# 16_LMS2_RF2_Misc.net
KiCad netlist of a schematic drawn in Altium Designer
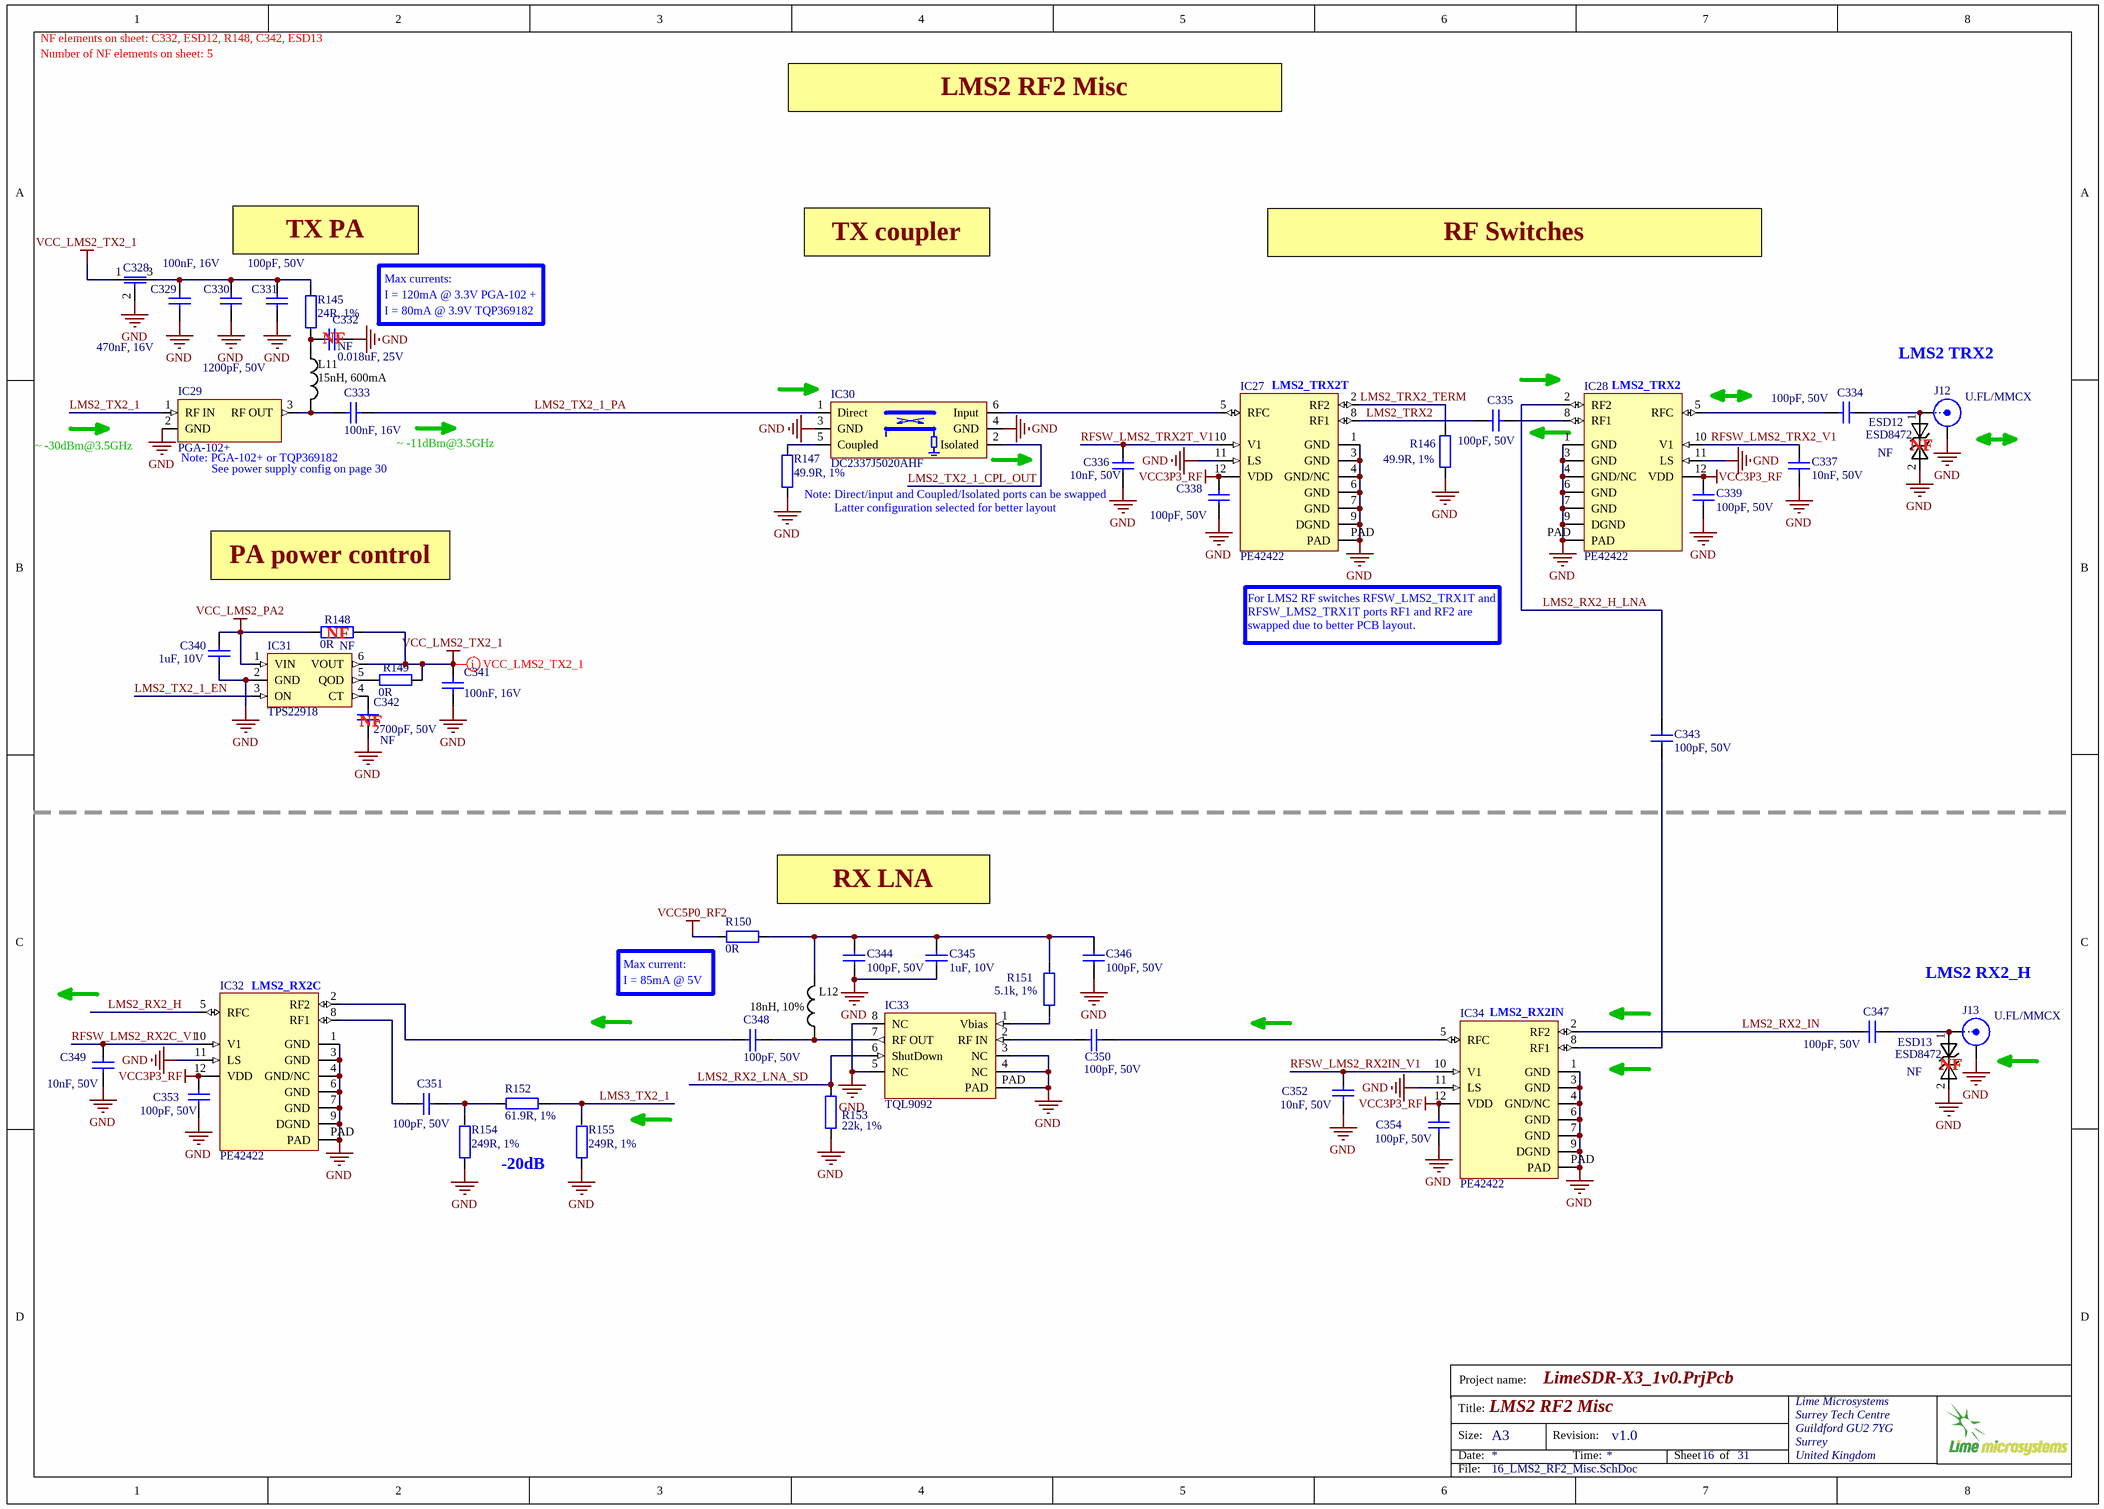
[diagram p0: 16_LMS2_RF2_Misc.SchDoc]

(export (version "E")
  (design (tool "Eeschema 10.0.6"))
  (components
    (comp (ref "C328")
      (value "470nF, 16V")
      (footprint "CAP0805_FEEDTHROUGH")
      (fields
        (field (name "MANUFACTURER") "Murata")
        (field (name "TOLERANCE") "20%")
        (field (name "VOLTAGE") "16V")
      )
      (libsource (lib "LimeMicroAltiumLib_schLib_r01") (part "Cap_feed_through"))
    )
    (comp (ref "C329")
      (value "100nF, 16V")
      (footprint "CAP0402")
      (fields (field (name "MANUFACTURER") "Murata Electronics") (field (name "TOLERANCE") "10 %"))
      (libsource (lib "") (part "Cap_0402_6"))
    )
    (comp (ref "C330")
      (value "1200pF, 50V")
      (footprint "CAP0402")
      (fields (field (name "MANUFACTURER") "Kemet") (field (name "TOLERANCE") "±5%"))
      (libsource (lib "") (part "Cap_0402_5"))
    )
    (comp (ref "C331")
      (value "100pF, 50V")
      (footprint "CAP0402")
      (fields (field (name "TOLERANCE") "±5%") (field (name "MANUFACTURER") "Yageo"))
      (libsource (lib "") (part "Cap_0402_6"))
    )
    (comp (ref "C332")
      (value "0.018uF, 25V")
      (footprint "CAP0402")
      (fields
        (field (name "ASSEMBLY INFO") "NF")
        (field (name "MANUFACTURER") "Yageo")
        (field (name "TOLERANCE") "10%")
      )
      (libsource (lib "") (part "Cap_0402_5"))
    )
    (comp (ref "C333")
      (value "100nF, 16V")
      (footprint "CAP0402")
      (fields (field (name "MANUFACTURER") "Murata Electronics") (field (name "TOLERANCE") "10 %"))
      (libsource (lib "") (part "Cap_0402_5"))
    )
    (comp (ref "C334")
      (value "100pF, 50V")
      (footprint "CAP0402")
      (fields (field (name "TOLERANCE") "±5%") (field (name "MANUFACTURER") "Yageo"))
      (libsource (lib "LimeMicroAltiumLib_schLib") (part "Cap_0402"))
    )
    (comp (ref "C335")
      (value "100pF, 50V")
      (footprint "CAP0402")
      (fields (field (name "TOLERANCE") "±5%") (field (name "MANUFACTURER") "Yageo"))
      (libsource (lib "LimeMicroAltiumLib_schLib") (part "Cap_0402"))
    )
    (comp (ref "C336")
      (value "10nF, 50V")
      (footprint "CAP0402")
      (fields
        (field (name "MANUFACTURER") "Murata Electronics North America")
        (field (name "TOLERANCE") "±10%")
      )
      (libsource (lib "") (part "Cap_0402_1"))
    )
    (comp (ref "C337")
      (value "10nF, 50V")
      (footprint "CAP0402")
      (fields
        (field (name "MANUFACTURER") "Murata Electronics North America")
        (field (name "TOLERANCE") "±10%")
      )
      (libsource (lib "") (part "Cap_0402_1"))
    )
    (comp (ref "C338")
      (value "100pF, 50V")
      (footprint "CAP0402")
      (fields (field (name "TOLERANCE") "±5%") (field (name "MANUFACTURER") "Yageo"))
      (libsource (lib "") (part "Cap_0402_10"))
    )
    (comp (ref "C339")
      (value "100pF, 50V")
      (footprint "CAP0402")
      (fields (field (name "TOLERANCE") "±5%") (field (name "MANUFACTURER") "Yageo"))
      (libsource (lib "") (part "Cap_0402_10"))
    )
    (comp (ref "C340")
      (value "1uF, 10V")
      (footprint "CAP0402")
      (fields (field (name "MANUFACTURER") "TDK"))
      (libsource (lib "") (part "Cap_0402_2"))
    )
    (comp (ref "C341")
      (value "100nF, 16V")
      (footprint "CAP0402")
      (fields (field (name "MANUFACTURER") "Murata Electronics") (field (name "TOLERANCE") "10 %"))
      (libsource (lib "") (part "Cap_0402_2"))
    )
    (comp (ref "C342")
      (value "2700pF, 50V")
      (footprint "CAP0402")
      (fields
        (field (name "ASSEMBLY INFO") "NF")
        (field (name "TOLERANCE") "±10%")
        (field (name "MANUFACTURER") "Murata Electronics North America")
      )
      (libsource (lib "") (part "Cap_0402_6"))
    )
    (comp (ref "C343")
      (value "100pF, 50V")
      (footprint "CAP0402")
      (fields (field (name "TOLERANCE") "±5%") (field (name "MANUFACTURER") "Yageo"))
      (libsource (lib "LimeMicroAltiumLib_schLib") (part "Cap_0402"))
    )
    (comp (ref "C344")
      (value "100pF, 50V")
      (footprint "CAP0402")
      (fields (field (name "TOLERANCE") "±5%") (field (name "MANUFACTURER") "Yageo"))
      (libsource (lib "") (part "Cap_0402_3"))
    )
    (comp (ref "C345")
      (value "1uF, 10V")
      (footprint "CAP0402")
      (fields (field (name "MANUFACTURER") "TDK"))
      (libsource (lib "") (part "Cap_0402_4"))
    )
    (comp (ref "C346")
      (value "100pF, 50V")
      (footprint "CAP0402")
      (fields (field (name "TOLERANCE") "±5%") (field (name "MANUFACTURER") "Yageo"))
      (libsource (lib "") (part "Cap_0402_3"))
    )
    (comp (ref "C347")
      (value "100pF, 50V")
      (footprint "CAP0402")
      (fields (field (name "TOLERANCE") "±5%") (field (name "MANUFACTURER") "Yageo"))
      (libsource (lib "LimeMicroAltiumLib_schLib") (part "Cap_0402"))
    )
    (comp (ref "C348")
      (value "100pF, 50V")
      (footprint "CAP0402")
      (fields (field (name "TOLERANCE") "±5%") (field (name "MANUFACTURER") "Yageo"))
      (libsource (lib "") (part "Cap_0402_2"))
    )
    (comp (ref "C349")
      (value "10nF, 50V")
      (footprint "CAP0402")
      (fields
        (field (name "MANUFACTURER") "Murata Electronics North America")
        (field (name "TOLERANCE") "±10%")
      )
      (libsource (lib "") (part "Cap_0402_8"))
    )
    (comp (ref "C350")
      (value "100pF, 50V")
      (footprint "CAP0402")
      (fields (field (name "TOLERANCE") "±5%") (field (name "MANUFACTURER") "Yageo"))
      (libsource (lib "") (part "Cap_0402_7"))
    )
    (comp (ref "C351")
      (value "100pF, 50V")
      (footprint "CAP0402")
      (fields (field (name "TOLERANCE") "±5%") (field (name "MANUFACTURER") "Yageo"))
      (libsource (lib "LimeMicroAltiumLib_schLib") (part "Cap_0402"))
    )
    (comp (ref "C352")
      (value "10nF, 50V")
      (footprint "CAP0402")
      (fields
        (field (name "MANUFACTURER") "Murata Electronics North America")
        (field (name "TOLERANCE") "±10%")
      )
      (libsource (lib "") (part "Cap_0402_5"))
    )
    (comp (ref "C353")
      (value "100pF, 50V")
      (footprint "CAP0402")
      (fields (field (name "TOLERANCE") "±5%") (field (name "MANUFACTURER") "Yageo"))
      (libsource (lib "") (part "Cap_0402_9"))
    )
    (comp (ref "C354")
      (value "100pF, 50V")
      (footprint "CAP0402")
      (fields (field (name "TOLERANCE") "±5%") (field (name "MANUFACTURER") "Yageo"))
      (libsource (lib "") (part "Cap_0402_5"))
    )
    (comp (ref "ESD12")
      (value "ESD8472")
      (footprint "ESD8472_X3DFN2")
      (fields (field (name "MANUFACTURER") "ON Semiconductor") (field (name "ASSEMBLY INFO") "NF"))
      (libsource (lib "LimeMicroAltiumLib_schLib") (part "ESD8472"))
    )
    (comp (ref "ESD13")
      (value "ESD8472")
      (footprint "ESD8472_X3DFN2")
      (fields (field (name "MANUFACTURER") "ON Semiconductor") (field (name "ASSEMBLY INFO") "NF"))
      (libsource (lib "") (part "ESD8472_1"))
    )
    (comp (ref "IC27")
      (value "PE42422")
      (footprint "PE42422_QFN12")
      (fields (field (name "MANUFACTURER") "Peregrine Semiconductor"))
      (libsource (lib "") (part "PE42422_1"))
    )
    (comp (ref "IC28")
      (value "PE42422")
      (footprint "PE42422_QFN12")
      (fields (field (name "MANUFACTURER") "Peregrine Semiconductor"))
      (libsource (lib "LimeMicroAltiumLib_schLib") (part "PE42422"))
    )
    (comp (ref "IC29")
      (value "PGA-102+")
      (footprint "PGA-102+_SOT89")
      (fields (field (name "MANUFACTURER") "Qorvo"))
      (libsource (lib "LimeMicroAltiumLib_schLib_r01") (part "PGA-102+_PA"))
    )
    (comp (ref "IC30")
      (value "DC2337J5020AHF")
      (footprint "DC2337J5020AHF_ANAREN_COUPLER_0805")
      (fields (field (name "MANUFACTURER") "Anaren"))
      (libsource (lib "LimeMicroAltiumLib_schLib_r02") (part "DC2337J5020AHF_coupler"))
    )
    (comp (ref "IC31")
      (value "TPS22918")
      (footprint "SOT23-6")
      (fields (field (name "MANUFACTURER") "Texas Instruments"))
      (libsource (lib "LimeMicroAltiumLib_schLib") (part "TPS22918"))
    )
    (comp (ref "IC32")
      (value "PE42422")
      (footprint "PE42422_QFN12")
      (fields (field (name "MANUFACTURER") "Peregrine Semiconductor"))
      (libsource (lib "") (part "PE42422_3"))
    )
    (comp (ref "IC33")
      (value "TQL9092")
      (footprint "TQL9092")
      (fields (field (name "MANUFACTURER") "Qorvo"))
      (libsource (lib "LimeMicroAltiumLib_schLib") (part "TQL9092"))
    )
    (comp (ref "IC34")
      (value "PE42422")
      (footprint "PE42422_QFN12")
      (fields (field (name "MANUFACTURER") "Peregrine Semiconductor"))
      (libsource (lib "") (part "PE42422_2"))
    )
    (comp (ref "J12")
      (value "U.FL/MMCX")
      (footprint "MMCX_UFL_conn_m")
      (description "CONN UMC RCPT STR 50 OHM SMD")
      (fields (field (name "MANUFACTURER") "Amphenol RF"))
      (libsource (lib "LimeMicroAltiumLib_schLib") (part "RF_IF_connector"))
    )
    (comp (ref "J13")
      (value "U.FL/MMCX")
      (footprint "MMCX_UFL_conn_m")
      (description "CONN UMC RCPT STR 50 OHM SMD")
      (fields (field (name "MANUFACTURER") "Amphenol RF"))
      (libsource (lib "LimeMicroAltiumLib_schLib") (part "RF_IF_connector"))
    )
    (comp (ref "L11")
      (value "15nH, 600mA")
      (footprint "RES0805")
      (fields (field (name "MANUFACTURER") "Bourns") (field (name "TOLERANCE") "5%"))
      (libsource (lib "LimeMicroAltiumLib_schLib") (part "Inductor_0603"))
    )
    (comp (ref "L12")
      (value "18nH, 10%")
      (footprint "RES0603")
      (fields (field (name "MANUFACTURER") "Pulse Electronics Network") (field (name "TOLERANCE") "±10%"))
      (libsource (lib "LimeMicroAltiumLib_schLib") (part "Inductor"))
    )
    (comp (ref "R145")
      (value "24R, 1%")
      (footprint "RES0402")
      (fields (field (name "MANUFACTURER") "Yageo") (field (name "TOLERANCE") "1%"))
      (libsource (lib "LimeFPGAboard_schLib") (part "Res_0402"))
    )
    (comp (ref "R146")
      (value "49.9R, 1%")
      (footprint "RES0402")
      (fields
        (field (name "TOLERANCE") "±1%")
        (field (name "MANUFACTURER") "Samsung Electro-Mechanics America, Inc.")
        (field (name "MANUFACTURER PART NUMBER") "RC1005F49R9CS")
      )
      (libsource (lib "LimeMicroAltiumLib_schLib") (part "Res_0402"))
    )
    (comp (ref "R147")
      (value "49.9R, 1%")
      (footprint "RES0402")
      (fields
        (field (name "TOLERANCE") "±1%")
        (field (name "MANUFACTURER") "Samsung Electro-Mechanics America, Inc.")
        (field (name "MANUFACTURER PART NUMBER") "RC1005F49R9CS")
      )
      (libsource (lib "LimeMicroAltiumLib_schLib") (part "Res_0402"))
    )
    (comp (ref "R148")
      (value "0R")
      (footprint "RES0402")
      (fields
        (field (name "ASSEMBLY INFO") "NF")
        (field (name "MANUFACTURER") "Yageo")
        (field (name "TOLERANCE") "Jumper")
      )
      (libsource (lib "") (part "Res_0402_1"))
    )
    (comp (ref "R149")
      (value "0R")
      (footprint "RES0402")
      (fields (field (name "MANUFACTURER") "Yageo") (field (name "TOLERANCE") "Jumper"))
      (libsource (lib "") (part "Res_0402_1"))
    )
    (comp (ref "R150")
      (value "0R")
      (footprint "RES0402")
      (fields (field (name "MANUFACTURER") "Yageo") (field (name "TOLERANCE") "Jumper"))
      (libsource (lib "LimeMicroAltiumLib_schLib") (part "Res_0402"))
    )
    (comp (ref "R151")
      (value "5.1k, 1%")
      (footprint "RES0603")
      (fields (field (name "MANUFACTURER") "Stackpole Electronics") (field (name "TOLERANCE") "1%"))
      (libsource (lib "LimeMicroAltiumLib_schLib") (part "Res_0603"))
    )
    (comp (ref "R152")
      (value "61.9R, 1%")
      (footprint "RES0402")
      (fields (field (name "MANUFACTURER") "Yageo") (field (name "TOLERANCE") "1%"))
      (libsource (lib "") (part "Res_0402_1"))
    )
    (comp (ref "R153")
      (value "22k, 1%")
      (footprint "RES0402")
      (fields (field (name "MANUFACTURER") "Yageo") (field (name "TOLERANCE") "±1%"))
      (libsource (lib "") (part "Res_0402_1"))
    )
    (comp (ref "R154")
      (value "249R, 1%")
      (footprint "RES0402")
      (fields (field (name "MANUFACTURER") "Stackpole Electronics Inc") (field (name "TOLERANCE") "±1%"))
      (libsource (lib "") (part "Res_0402_1"))
    )
    (comp (ref "R155")
      (value "249R, 1%")
      (footprint "RES0402")
      (fields (field (name "MANUFACTURER") "Stackpole Electronics Inc") (field (name "TOLERANCE") "±1%"))
      (libsource (lib "") (part "Res_0402_1"))
    )
  )
  (nets
    (net (code "1") (name "/LMS2_RX2_H") (class "Default")
      (node (ref "IC32") (pin "5") (pinfunction "RFC_5") (pintype "bidirectional"))
    )
    (net (code "2") (name "/LMS2_RX2_H_LNA") (class "Default")
      (node (ref "C343") (pin "2") (pinfunction "2_2") (pintype "passive"))
      (node (ref "IC28") (pin "2") (pinfunction "RF2_2") (pintype "bidirectional"))
    )
    (net (code "3") (name "/LMS2_RX2_IN") (class "Default")
      (node (ref "C347") (pin "1") (pinfunction "1_1") (pintype "passive"))
      (node (ref "IC34") (pin "2") (pinfunction "RF2_2") (pintype "bidirectional"))
    )
    (net (code "4") (name "/LMS2_RX2_LNA_SD") (class "Default")
      (node (ref "IC33") (pin "6") (pinfunction "ShutDown_6") (pintype "input"))
      (node (ref "R153") (pin "2") (pinfunction "2_2") (pintype "passive"))
    )
    (net (code "5") (name "/LMS2_TRX2") (class "Default")
      (node (ref "C335") (pin "1") (pinfunction "1_1") (pintype "passive"))
      (node (ref "IC27") (pin "8") (pinfunction "RF1_8") (pintype "bidirectional"))
    )
    (net (code "6") (name "/LMS2_TRX2_TERM") (class "Default")
      (node (ref "IC27") (pin "2") (pinfunction "RF2_2") (pintype "bidirectional"))
      (node (ref "R146") (pin "1") (pinfunction "1_1") (pintype "passive"))
    )
    (net (code "7") (name "/LMS2_TX2_1") (class "Default")
      (node (ref "IC29") (pin "1") (pinfunction "RF_IN_1") (pintype "input"))
    )
    (net (code "8") (name "/LMS2_TX2_1_CPL_OUT") (class "Default")
      (node (ref "IC30") (pin "2") (pinfunction "Isolated_2") (pintype "passive"))
    )
    (net (code "9") (name "/LMS2_TX2_1_EN") (class "Default")
      (node (ref "IC31") (pin "3") (pinfunction "ON_3") (pintype "input"))
    )
    (net (code "10") (name "/LMS2_TX2_1_PA") (class "Default")
      (node (ref "C333") (pin "1") (pinfunction "1_1") (pintype "passive"))
      (node (ref "IC30") (pin "1") (pinfunction "Direct_1") (pintype "passive"))
    )
    (net (code "11") (name "/LMS3_TX2_1") (class "Default")
      (node (ref "R152") (pin "2") (pinfunction "2_2") (pintype "passive"))
      (node (ref "R155") (pin "2") (pinfunction "2_2") (pintype "passive"))
    )
    (net (code "12") (name "/RFSW_LMS2_RX2C_V1") (class "Default")
      (node (ref "C349") (pin "1") (pinfunction "1_1") (pintype "passive"))
      (node (ref "IC32") (pin "10") (pinfunction "V1_10") (pintype "input"))
    )
    (net (code "13") (name "/RFSW_LMS2_RX2IN_V1") (class "Default")
      (node (ref "C352") (pin "1") (pinfunction "1_1") (pintype "passive"))
      (node (ref "IC34") (pin "10") (pinfunction "V1_10") (pintype "input"))
    )
    (net (code "14") (name "/RFSW_LMS2_TRX2T_V1") (class "Default")
      (node (ref "C336") (pin "1") (pinfunction "1_1") (pintype "passive"))
      (node (ref "IC27") (pin "10") (pinfunction "V1_10") (pintype "input"))
    )
    (net (code "15") (name "/RFSW_LMS2_TRX2_V1") (class "Default")
      (node (ref "C337") (pin "1") (pinfunction "1_1") (pintype "passive"))
      (node (ref "IC28") (pin "10") (pinfunction "V1_10") (pintype "input"))
    )
    (net (code "16") (name "GND") (class "Default")
      (node (ref "C328") (pin "2") (pinfunction "2_2") (pintype "passive"))
      (node (ref "C329") (pin "1") (pinfunction "1_1") (pintype "passive"))
      (node (ref "C330") (pin "2") (pinfunction "2_2") (pintype "passive"))
      (node (ref "C331") (pin "2") (pinfunction "2_2") (pintype "passive"))
      (node (ref "C332") (pin "2") (pinfunction "2_2") (pintype "passive"))
      (node (ref "C336") (pin "2") (pinfunction "2_2") (pintype "passive"))
      (node (ref "C337") (pin "2") (pinfunction "2_2") (pintype "passive"))
      (node (ref "C338") (pin "1") (pinfunction "1_1") (pintype "passive"))
      (node (ref "C339") (pin "1") (pinfunction "1_1") (pintype "passive"))
      (node (ref "C340") (pin "1") (pinfunction "1_1") (pintype "passive"))
      (node (ref "C341") (pin "1") (pinfunction "1_1") (pintype "passive"))
      (node (ref "C342") (pin "2") (pinfunction "2_2") (pintype "passive"))
      (node (ref "C344") (pin "2") (pinfunction "2_2") (pintype "passive"))
      (node (ref "C345") (pin "1") (pinfunction "1_1") (pintype "passive"))
      (node (ref "C346") (pin "2") (pinfunction "2_2") (pintype "passive"))
      (node (ref "C349") (pin "2") (pinfunction "2_2") (pintype "passive"))
      (node (ref "C352") (pin "2") (pinfunction "2_2") (pintype "passive"))
      (node (ref "C353") (pin "1") (pinfunction "1_1") (pintype "passive"))
      (node (ref "C354") (pin "1") (pinfunction "1_1") (pintype "passive"))
      (node (ref "ESD12") (pin "2") (pinfunction "2_2") (pintype "passive"))
      (node (ref "ESD13") (pin "2") (pinfunction "2_2") (pintype "passive"))
      (node (ref "IC27") (pin "1") (pinfunction "GND_1") (pintype "passive"))
      (node (ref "IC27") (pin "11") (pinfunction "LS_11") (pintype "input"))
      (node (ref "IC27") (pin "3") (pinfunction "GND_3") (pintype "passive"))
      (node (ref "IC27") (pin "4") (pinfunction "GND/NC_4") (pintype "passive"))
      (node (ref "IC27") (pin "6") (pinfunction "GND_6") (pintype "passive"))
      (node (ref "IC27") (pin "7") (pinfunction "GND_7") (pintype "passive"))
      (node (ref "IC27") (pin "9") (pinfunction "DGND_9") (pintype "passive"))
      (node (ref "IC27") (pin "PAD") (pinfunction "PAD_PAD") (pintype "passive"))
      (node (ref "IC28") (pin "1") (pinfunction "GND_1") (pintype "passive"))
      (node (ref "IC28") (pin "11") (pinfunction "LS_11") (pintype "input"))
      (node (ref "IC28") (pin "3") (pinfunction "GND_3") (pintype "passive"))
      (node (ref "IC28") (pin "4") (pinfunction "GND/NC_4") (pintype "passive"))
      (node (ref "IC28") (pin "6") (pinfunction "GND_6") (pintype "passive"))
      (node (ref "IC28") (pin "7") (pinfunction "GND_7") (pintype "passive"))
      (node (ref "IC28") (pin "9") (pinfunction "DGND_9") (pintype "passive"))
      (node (ref "IC28") (pin "PAD") (pinfunction "PAD_PAD") (pintype "passive"))
      (node (ref "IC29") (pin "2") (pinfunction "GND_2") (pintype "passive"))
      (node (ref "IC30") (pin "3") (pinfunction "GND_3") (pintype "passive"))
      (node (ref "IC30") (pin "4") (pinfunction "GND_4") (pintype "passive"))
      (node (ref "IC31") (pin "2") (pinfunction "GND_2") (pintype "passive"))
      (node (ref "IC32") (pin "1") (pinfunction "GND_1") (pintype "passive"))
      (node (ref "IC32") (pin "11") (pinfunction "LS_11") (pintype "input"))
      (node (ref "IC32") (pin "3") (pinfunction "GND_3") (pintype "passive"))
      (node (ref "IC32") (pin "4") (pinfunction "GND/NC_4") (pintype "passive"))
      (node (ref "IC32") (pin "6") (pinfunction "GND_6") (pintype "passive"))
      (node (ref "IC32") (pin "7") (pinfunction "GND_7") (pintype "passive"))
      (node (ref "IC32") (pin "9") (pinfunction "DGND_9") (pintype "passive"))
      (node (ref "IC32") (pin "PAD") (pinfunction "PAD_PAD") (pintype "passive"))
      (node (ref "IC33") (pin "3") (pinfunction "NC_3") (pintype "passive"))
      (node (ref "IC33") (pin "4") (pinfunction "NC_4") (pintype "passive"))
      (node (ref "IC33") (pin "5") (pinfunction "NC_5") (pintype "passive"))
      (node (ref "IC33") (pin "8") (pinfunction "NC_8") (pintype "passive"))
      (node (ref "IC33") (pin "PAD") (pinfunction "PAD_PAD") (pintype "passive"))
      (node (ref "IC34") (pin "1") (pinfunction "GND_1") (pintype "passive"))
      (node (ref "IC34") (pin "11") (pinfunction "LS_11") (pintype "input"))
      (node (ref "IC34") (pin "3") (pinfunction "GND_3") (pintype "passive"))
      (node (ref "IC34") (pin "4") (pinfunction "GND/NC_4") (pintype "passive"))
      (node (ref "IC34") (pin "6") (pinfunction "GND_6") (pintype "passive"))
      (node (ref "IC34") (pin "7") (pinfunction "GND_7") (pintype "passive"))
      (node (ref "IC34") (pin "9") (pinfunction "DGND_9") (pintype "passive"))
      (node (ref "IC34") (pin "PAD") (pinfunction "PAD_PAD") (pintype "passive"))
      (node (ref "J12") (pin "2") (pinfunction "Y_2") (pintype "passive"))
      (node (ref "J13") (pin "2") (pinfunction "Y_2") (pintype "passive"))
      (node (ref "R146") (pin "2") (pinfunction "2_2") (pintype "passive"))
      (node (ref "R147") (pin "2") (pinfunction "2_2") (pintype "passive"))
      (node (ref "R153") (pin "1") (pinfunction "1_1") (pintype "passive"))
      (node (ref "R154") (pin "1") (pinfunction "1_1") (pintype "passive"))
      (node (ref "R155") (pin "1") (pinfunction "1_1") (pintype "passive"))
    )
    (net (code "17") (name "Net-(C328-Pad3)") (class "Default")
      (node (ref "C328") (pin "3") (pinfunction "3_3") (pintype "passive"))
      (node (ref "C329") (pin "2") (pinfunction "2_2") (pintype "passive"))
      (node (ref "C330") (pin "1") (pinfunction "1_1") (pintype "passive"))
      (node (ref "C331") (pin "1") (pinfunction "1_1") (pintype "passive"))
      (node (ref "R145") (pin "1") (pinfunction "1_1") (pintype "passive"))
    )
    (net (code "18") (name "Net-(C332-Pad1)") (class "Default")
      (node (ref "C332") (pin "1") (pinfunction "1_1") (pintype "passive"))
      (node (ref "L11") (pin "1") (pinfunction "1_1") (pintype "passive"))
      (node (ref "R145") (pin "2") (pinfunction "2_2") (pintype "passive"))
    )
    (net (code "19") (name "Net-(C344-Pad1)") (class "Default")
      (node (ref "C344") (pin "1") (pinfunction "1_1") (pintype "passive"))
      (node (ref "C345") (pin "2") (pinfunction "2_2") (pintype "passive"))
      (node (ref "C346") (pin "1") (pinfunction "1_1") (pintype "passive"))
      (node (ref "L12") (pin "1") (pinfunction "1_1") (pintype "passive"))
      (node (ref "R150") (pin "2") (pinfunction "2_2") (pintype "passive"))
      (node (ref "R151") (pin "2") (pinfunction "2_2") (pintype "passive"))
    )
    (net (code "20") (name "Net-(C351-Pad1)") (class "Default")
      (node (ref "C351") (pin "1") (pinfunction "1_1") (pintype "passive"))
      (node (ref "R152") (pin "1") (pinfunction "1_1") (pintype "passive"))
      (node (ref "R154") (pin "2") (pinfunction "2_2") (pintype "passive"))
    )
    (net (code "21") (name "Net-(IC27-RFC)") (class "Default")
      (node (ref "IC27") (pin "5") (pinfunction "RFC_5") (pintype "bidirectional"))
      (node (ref "IC30") (pin "6") (pinfunction "Input_6") (pintype "passive"))
    )
    (net (code "22") (name "Net-(IC28-RF1)") (class "Default")
      (node (ref "C335") (pin "2") (pinfunction "2_2") (pintype "passive"))
      (node (ref "IC28") (pin "8") (pinfunction "RF1_8") (pintype "bidirectional"))
    )
    (net (code "23") (name "Net-(IC28-RFC)") (class "Default")
      (node (ref "C334") (pin "1") (pinfunction "1_1") (pintype "passive"))
      (node (ref "IC28") (pin "5") (pinfunction "RFC_5") (pintype "bidirectional"))
    )
    (net (code "24") (name "Net-(IC29-RF_OUT)") (class "Default")
      (node (ref "C333") (pin "2") (pinfunction "2_2") (pintype "passive"))
      (node (ref "IC29") (pin "3") (pinfunction "RF_OUT_3") (pintype "output"))
      (node (ref "L11") (pin "2") (pinfunction "2_2") (pintype "passive"))
    )
    (net (code "25") (name "Net-(IC30-Coupled)") (class "Default")
      (node (ref "IC30") (pin "5") (pinfunction "Coupled_5") (pintype "passive"))
      (node (ref "R147") (pin "1") (pinfunction "1_1") (pintype "passive"))
    )
    (net (code "26") (name "Net-(IC31-CT)") (class "Default")
      (node (ref "C342") (pin "1") (pinfunction "1_1") (pintype "passive"))
      (node (ref "IC31") (pin "4") (pinfunction "CT_4") (pintype "output"))
    )
    (net (code "27") (name "Net-(IC31-QOD)") (class "Default")
      (node (ref "IC31") (pin "5") (pinfunction "QOD_5") (pintype "output"))
      (node (ref "R149") (pin "2") (pinfunction "2_2") (pintype "passive"))
    )
    (net (code "28") (name "Net-(IC32-RF1)") (class "Default")
      (node (ref "C351") (pin "2") (pinfunction "2_2") (pintype "passive"))
      (node (ref "IC32") (pin "8") (pinfunction "RF1_8") (pintype "bidirectional"))
    )
    (net (code "29") (name "Net-(IC32-RF2)") (class "Default")
      (node (ref "C348") (pin "1") (pinfunction "1_1") (pintype "passive"))
      (node (ref "IC32") (pin "2") (pinfunction "RF2_2") (pintype "bidirectional"))
    )
    (net (code "30") (name "Net-(IC33-RF_IN)") (class "Default")
      (node (ref "C350") (pin "1") (pinfunction "1_1") (pintype "passive"))
      (node (ref "IC33") (pin "2") (pinfunction "RF_IN_2") (pintype "input"))
    )
    (net (code "31") (name "Net-(IC33-RF_OUT)") (class "Default")
      (node (ref "C348") (pin "2") (pinfunction "2_2") (pintype "passive"))
      (node (ref "IC33") (pin "7") (pinfunction "RF_OUT_7") (pintype "output"))
      (node (ref "L12") (pin "2") (pinfunction "2_2") (pintype "passive"))
    )
    (net (code "32") (name "Net-(IC33-Vbias)") (class "Default")
      (node (ref "IC33") (pin "1") (pinfunction "Vbias_1") (pintype "input"))
      (node (ref "R151") (pin "1") (pinfunction "1_1") (pintype "passive"))
    )
    (net (code "33") (name "Net-(IC34-RF1)") (class "Default")
      (node (ref "C343") (pin "1") (pinfunction "1_1") (pintype "passive"))
      (node (ref "IC34") (pin "8") (pinfunction "RF1_8") (pintype "bidirectional"))
    )
    (net (code "34") (name "Net-(IC34-RFC)") (class "Default")
      (node (ref "C350") (pin "2") (pinfunction "2_2") (pintype "passive"))
      (node (ref "IC34") (pin "5") (pinfunction "RFC_5") (pintype "bidirectional"))
    )
    (net (code "35") (name "Net-(J12-X)") (class "Default")
      (node (ref "C334") (pin "2") (pinfunction "2_2") (pintype "passive"))
      (node (ref "ESD12") (pin "1") (pinfunction "1_1") (pintype "passive"))
      (node (ref "J12") (pin "1") (pinfunction "X_1") (pintype "passive"))
    )
    (net (code "36") (name "Net-(J13-X)") (class "Default")
      (node (ref "C347") (pin "2") (pinfunction "2_2") (pintype "passive"))
      (node (ref "ESD13") (pin "1") (pinfunction "1_1") (pintype "passive"))
      (node (ref "J13") (pin "1") (pinfunction "X_1") (pintype "passive"))
    )
    (net (code "37") (name "VCC3P3_RF") (class "Default")
      (node (ref "C338") (pin "2") (pinfunction "2_2") (pintype "passive"))
      (node (ref "C339") (pin "2") (pinfunction "2_2") (pintype "passive"))
      (node (ref "C353") (pin "2") (pinfunction "2_2") (pintype "passive"))
      (node (ref "C354") (pin "2") (pinfunction "2_2") (pintype "passive"))
      (node (ref "IC27") (pin "12") (pinfunction "VDD_12") (pintype "power_in"))
      (node (ref "IC28") (pin "12") (pinfunction "VDD_12") (pintype "power_in"))
      (node (ref "IC32") (pin "12") (pinfunction "VDD_12") (pintype "power_in"))
      (node (ref "IC34") (pin "12") (pinfunction "VDD_12") (pintype "power_in"))
    )
    (net (code "38") (name "VCC5P0_RF2") (class "Default")
      (node (ref "R150") (pin "1") (pinfunction "1_1") (pintype "passive"))
    )
    (net (code "39") (name "VCC_LMS2_PA2") (class "Default")
      (node (ref "C340") (pin "2") (pinfunction "2_2") (pintype "passive"))
      (node (ref "IC31") (pin "1") (pinfunction "VIN_1") (pintype "input"))
      (node (ref "R148") (pin "2") (pinfunction "2_2") (pintype "passive"))
    )
    (net (code "40") (name "VCC_LMS2_TX2_1") (class "Default")
      (node (ref "C328") (pin "1") (pinfunction "1_1") (pintype "passive"))
      (node (ref "C341") (pin "2") (pinfunction "2_2") (pintype "passive"))
      (node (ref "IC31") (pin "6") (pinfunction "VOUT_6") (pintype "output"))
      (node (ref "R148") (pin "1") (pinfunction "1_1") (pintype "passive"))
      (node (ref "R149") (pin "1") (pinfunction "1_1") (pintype "passive"))
    )
  )
)
